# Schematic_MicroBot_Voltage_Regulator_V1.net
KiCad netlist of a schematic drawn in Altium Designer
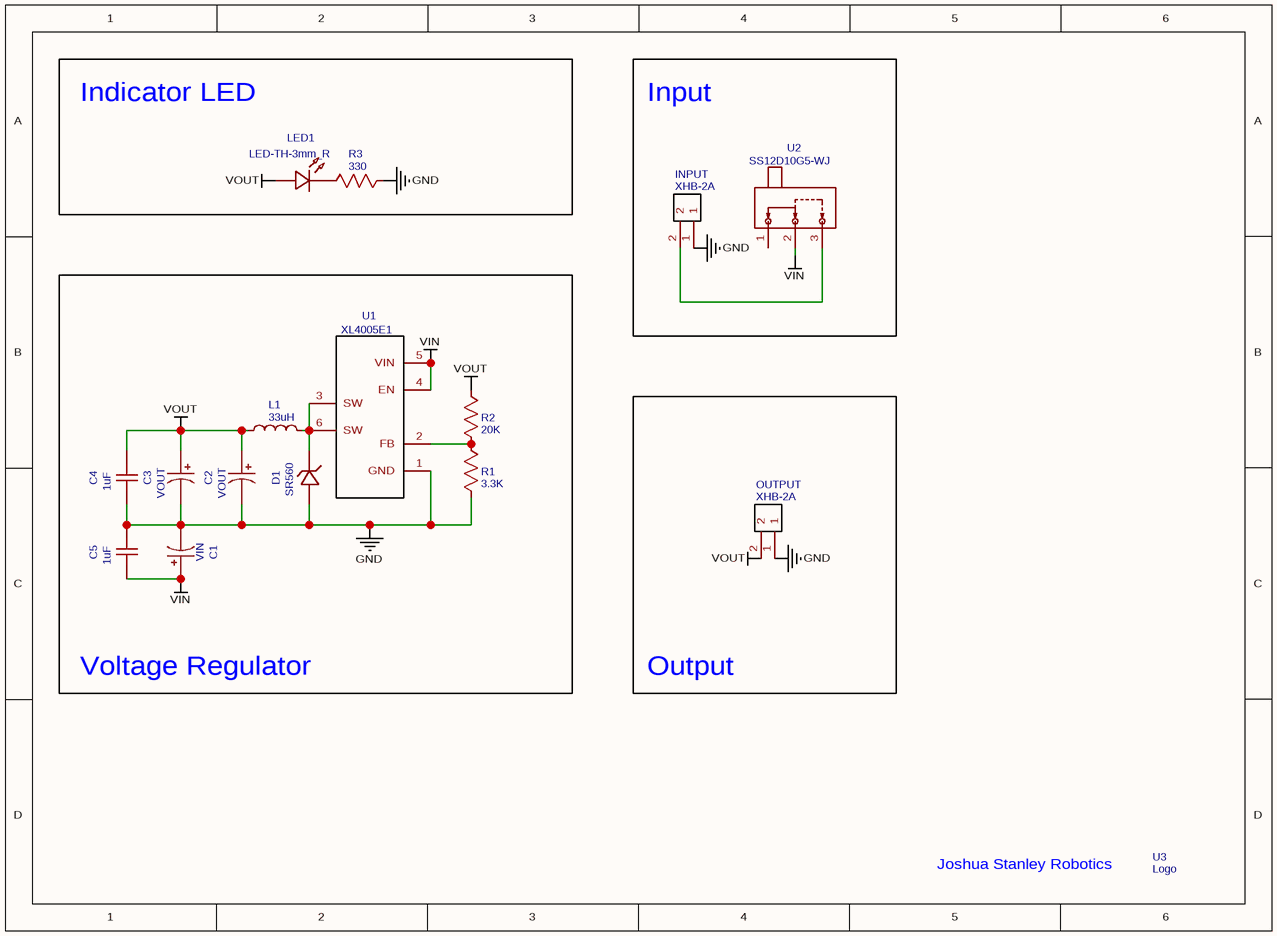
[diagram p0: Schematic_MicroBot Voltage Regulator V1.schdoc]

(export (version "E")
  (design (tool "Eeschema 10.0.6"))
  (components
    (comp (ref "C1")
      (value "VIN")
      (fields (field (name "CONTRIBUTOR") "LCEDA_Lib"))
      (libsource (lib "altium-import") (part "root_1_VIN_"))
    )
    (comp (ref "C2")
      (value "VOUT")
      (fields (field (name "CONTRIBUTOR") "LCEDA_Lib"))
      (libsource (lib "altium-import") (part "root_3_VOUT_"))
    )
    (comp (ref "C3")
      (value "VOUT")
      (fields (field (name "CONTRIBUTOR") "LCEDA_Lib"))
      (libsource (lib "altium-import") (part "root_3_VOUT_"))
    )
    (comp (ref "C4")
      (value "1uF")
      (fields (field (name "CONTRIBUTOR") "LCEDA_Lib"))
      (libsource (lib "altium-import") (part "root_3_1uF_"))
    )
    (comp (ref "C5")
      (value "1uF")
      (fields (field (name "CONTRIBUTOR") "LCEDA_Lib"))
      (libsource (lib "altium-import") (part "root_3_1uF_"))
    )
    (comp (ref "D1")
      (value "SR560")
      (fields (field (name "MANUFACTURER") "LGE(鲁光)") (field (name "CONTRIBUTOR") "LCSC"))
      (libsource (lib "altium-import") (part "root_3_SR560_"))
    )
    (comp (ref "INPUT")
      (value "XHB-2A")
      (fields (field (name "MANUFACTURER") "BOOMELE(博穆精密)"))
      (libsource (lib "altium-import") (part "root_3_XHB-2A_"))
    )
    (comp (ref "L1")
      (value "33uH")
      (fields
        (field (name "MANUFACTURER") "SHOU HAN(首韩)")
        (field (name "MANUFACTURER PART") "CYH127-33UH")
        (field (name "CONTRIBUTOR") "LCSC")
      )
      (libsource (lib "altium-import") (part "root_0_33uH_"))
    )
    (comp (ref "LED1")
      (value "LED-TH-3mm_R")
      (fields
        (field (name "MANUFACTURER") "EVERLIGHT(台湾亿光)")
        (field (name "MANUFACTURER PART") "204-10SDRD/S530-A3-L")
        (field (name "CONTRIBUTOR") "LCEDA_Lib")
      )
      (libsource (lib "altium-import") (part "root_0_LED-TH-3mm_R_"))
    )
    (comp (ref "OUTPUT")
      (value "XHB-2A")
      (fields (field (name "MANUFACTURER") "BOOMELE(博穆精密)"))
      (libsource (lib "altium-import") (part "root_3_XHB-2A_"))
    )
    (comp (ref "R1")
      (value "3.3K")
      (fields (field (name "CONTRIBUTOR") "LCEDA_Lib"))
      (libsource (lib "altium-import") (part "root_3_3.3K_"))
    )
    (comp (ref "R2")
      (value "20K")
      (fields (field (name "CONTRIBUTOR") "LCEDA_Lib"))
      (libsource (lib "altium-import") (part "root_3_20K_"))
    )
    (comp (ref "R3")
      (value "330")
      (fields (field (name "CONTRIBUTOR") "LCEDA_Lib"))
      (libsource (lib "altium-import") (part "root_0_330_"))
    )
    (comp (ref "U1")
      (value "XL4005E1")
      (fields (field (name "MANUFACTURER") "XLSEMI(芯龙)"))
      (libsource (lib "altium-import") (part "root_0_XL4005E1_"))
    )
    (comp (ref "U2")
      (value "SS12D10G5-WJ")
      (fields (field (name "MANUFACTURER") "SHOU HAN(首韩)") (field (name "CONTRIBUTOR") "lcsc"))
      (libsource (lib "altium-import") (part "root_0_SS12D10G5-WJ_"))
    )
    (comp (ref "U3")
      (value "Logo")
      (fields (field (name "CONTRIBUTOR") "jstan3546"))
      (libsource (lib "altium-import") (part "root_0_Logo_"))
    )
  )
  (nets
    (net (code "1") (name "GND") (class "Default")
      (node (ref "C1") (pin "2") (pinfunction "2_2") (pintype "passive"))
      (node (ref "C2") (pin "2") (pinfunction "2_2") (pintype "passive"))
      (node (ref "C3") (pin "2") (pinfunction "2_2") (pintype "passive"))
      (node (ref "C4") (pin "2") (pinfunction "2_2") (pintype "passive"))
      (node (ref "C5") (pin "1") (pinfunction "1_1") (pintype "passive"))
      (node (ref "D1") (pin "1") (pinfunction "A_1") (pintype "passive"))
      (node (ref "INPUT") (pin "1") (pinfunction "1_1") (pintype "passive"))
      (node (ref "OUTPUT") (pin "1") (pinfunction "1_1") (pintype "passive"))
      (node (ref "R1") (pin "2") (pinfunction "2_2") (pintype "passive"))
      (node (ref "R3") (pin "2") (pinfunction "2_2") (pintype "passive"))
      (node (ref "U1") (pin "1") (pinfunction "GND_1") (pintype "passive"))
    )
    (net (code "2") (name "Net-(D1-C)") (class "Default")
      (node (ref "D1") (pin "2") (pinfunction "C_2") (pintype "passive"))
      (node (ref "L1") (pin "2") (pinfunction "2_2") (pintype "passive"))
      (node (ref "U1") (pin "3") (pinfunction "SW_3") (pintype "passive"))
      (node (ref "U1") (pin "6") (pinfunction "SW_6") (pintype "passive"))
    )
    (net (code "3") (name "Net-(INPUT-Pad2)") (class "Default")
      (node (ref "INPUT") (pin "2") (pinfunction "2_2") (pintype "passive"))
      (node (ref "U2") (pin "3") (pinfunction "3_3") (pintype "passive"))
    )
    (net (code "4") (name "Net-(LED1-Pad2)") (class "Default")
      (node (ref "LED1") (pin "2") (pinfunction "2_2") (pintype "passive"))
      (node (ref "R3") (pin "1") (pinfunction "1_1") (pintype "passive"))
    )
    (net (code "5") (name "Net-(U1-FB)") (class "Default")
      (node (ref "R1") (pin "1") (pinfunction "1_1") (pintype "passive"))
      (node (ref "R2") (pin "2") (pinfunction "2_2") (pintype "passive"))
      (node (ref "U1") (pin "2") (pinfunction "FB_2") (pintype "passive"))
    )
    (net (code "6") (name "VIN") (class "Default")
      (node (ref "C1") (pin "1") (pinfunction "1_1") (pintype "passive"))
      (node (ref "C5") (pin "2") (pinfunction "2_2") (pintype "passive"))
      (node (ref "U1") (pin "4") (pinfunction "EN_4") (pintype "passive"))
      (node (ref "U1") (pin "5") (pinfunction "VIN_5") (pintype "passive"))
      (node (ref "U2") (pin "2") (pinfunction "2_2") (pintype "passive"))
    )
    (net (code "7") (name "VOUT") (class "Default")
      (node (ref "C2") (pin "1") (pinfunction "1_1") (pintype "passive"))
      (node (ref "C3") (pin "1") (pinfunction "1_1") (pintype "passive"))
      (node (ref "C4") (pin "1") (pinfunction "1_1") (pintype "passive"))
      (node (ref "L1") (pin "1") (pinfunction "1_1") (pintype "passive"))
      (node (ref "LED1") (pin "1") (pinfunction "1_1") (pintype "passive"))
      (node (ref "OUTPUT") (pin "2") (pinfunction "2_2") (pintype "passive"))
      (node (ref "R2") (pin "1") (pinfunction "1_1") (pintype "passive"))
    )
    (net (code "8") (name "unconnected-(U2-Pad1)") (class "Default")
      (node (ref "U2") (pin "1") (pinfunction "1_1") (pintype "passive"))
    )
  )
)
